# 02.net
KiCad netlist of a schematic drawn in Altium Designer
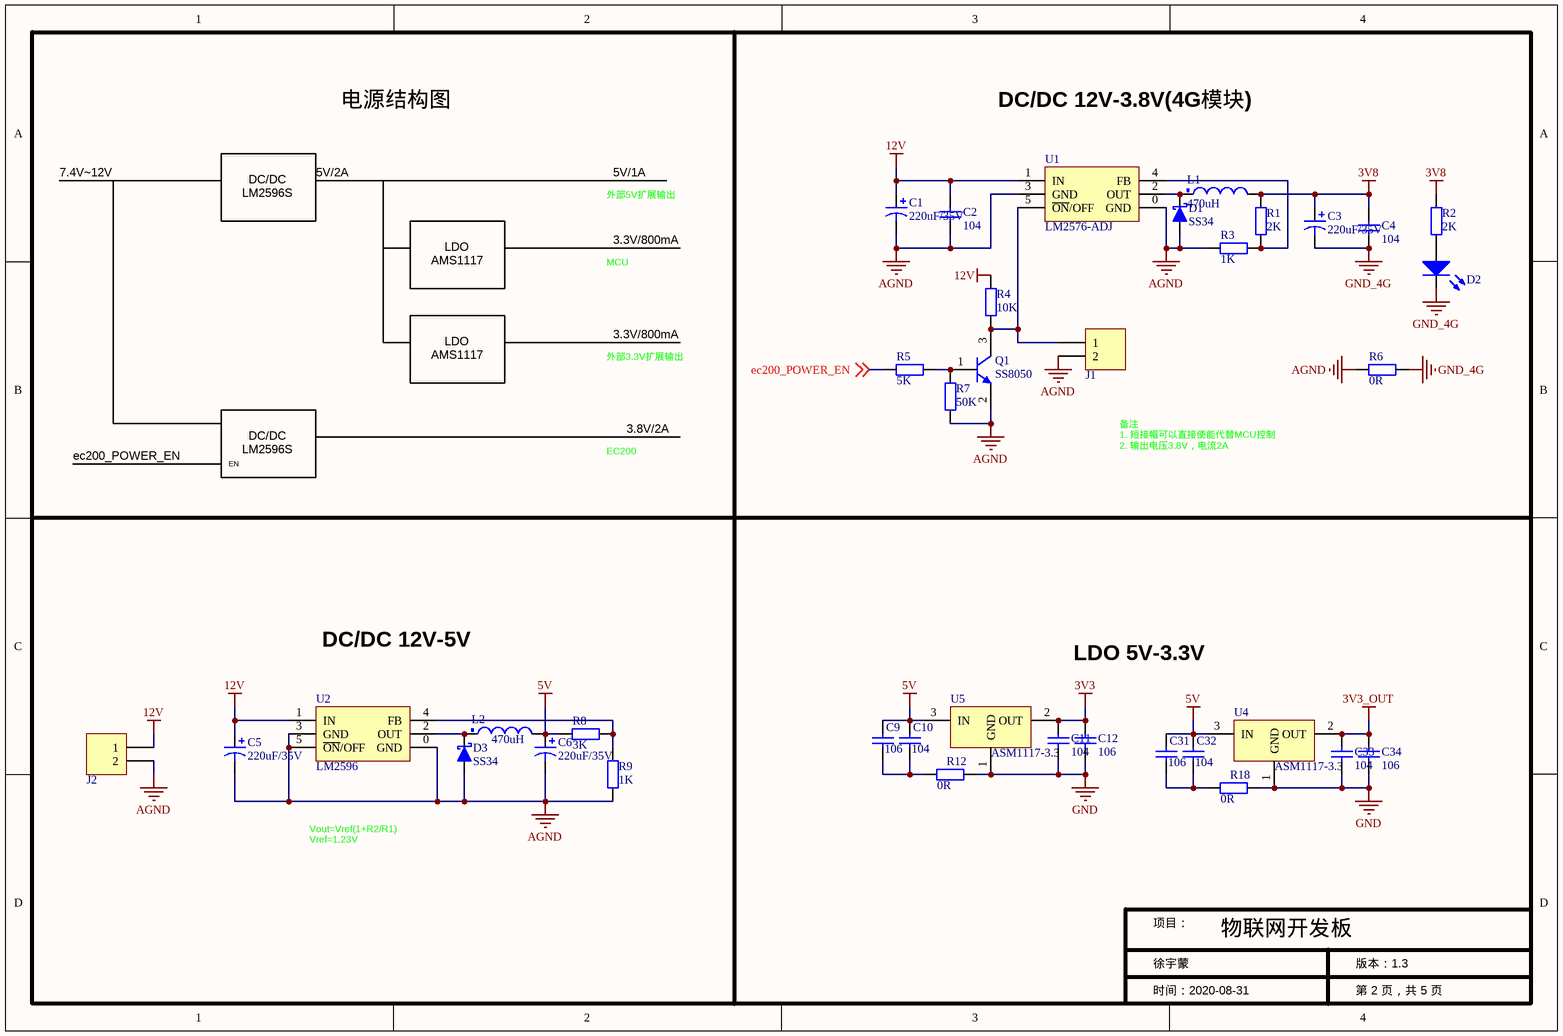
[diagram p0: 02_电源部分.SchDoc]

(export (version "E")
  (design (tool "Eeschema 10.0.6"))
  (components
    (comp (ref "C1")
      (value "220uF/35V")
      (footprint "Cap8x10.5mm")
      (description "贴片电解电容 8*10.5mm")
      (fields (field (name "Comment") "Cap Pol") (field (name "PUBLISHER") "Altium Limited"))
      (libsource (lib "元件库") (part "Cap Pol"))
    )
    (comp (ref "C2")
      (value "104")
      (footprint "CAP-0603")
      (description "无极性电容")
      (fields (field (name "Comment") "Cap") (field (name "PUBLISHER") "Altium Limited"))
      (libsource (lib "Arrowy_Racing") (part "Cap"))
    )
    (comp (ref "C3")
      (value "220uF/35V")
      (footprint "Cap8x10.5mm")
      (description "贴片电解电容 8*10.5mm")
      (fields (field (name "Comment") "Cap Pol") (field (name "PUBLISHER") "Altium Limited"))
      (libsource (lib "元件库") (part "Cap Pol"))
    )
    (comp (ref "C4")
      (value "104")
      (footprint "CAP-0603")
      (description "无极性电容")
      (fields (field (name "Comment") "Cap") (field (name "PUBLISHER") "Altium Limited"))
      (libsource (lib "Arrowy_Racing") (part "Cap"))
    )
    (comp (ref "C5")
      (value "220uF/35V")
      (footprint "Cap8x10.5mm")
      (description "贴片电解电容 8*10.5mm")
      (fields (field (name "Comment") "Cap Pol") (field (name "PUBLISHER") "Altium Limited"))
      (libsource (lib "元件库") (part "Cap Pol"))
    )
    (comp (ref "C6")
      (value "220uF/35V")
      (footprint "Cap8x10.5mm")
      (description "贴片电解电容 8*10.5mm")
      (fields (field (name "Comment") "Cap Pol") (field (name "PUBLISHER") "Altium Limited"))
      (libsource (lib "元件库") (part "Cap Pol"))
    )
    (comp (ref "C9")
      (value "106")
      (footprint "CAP-0603")
      (description "无极性电容")
      (fields (field (name "Comment") "Cap") (field (name "PUBLISHER") "Altium Limited"))
      (libsource (lib "Arrowy_Racing") (part "Cap"))
    )
    (comp (ref "C10")
      (value "104")
      (footprint "CAP-0603")
      (description "无极性电容")
      (fields (field (name "Comment") "Cap") (field (name "PUBLISHER") "Altium Limited"))
      (libsource (lib "Arrowy_Racing") (part "Cap"))
    )
    (comp (ref "C11")
      (value "104")
      (footprint "CAP-0603")
      (description "无极性电容")
      (fields (field (name "Comment") "Cap") (field (name "PUBLISHER") "Altium Limited"))
      (libsource (lib "Arrowy_Racing") (part "Cap"))
    )
    (comp (ref "C12")
      (value "106")
      (footprint "CAP-0603")
      (description "无极性电容")
      (fields (field (name "Comment") "Cap") (field (name "PUBLISHER") "Altium Limited"))
      (libsource (lib "Arrowy_Racing") (part "Cap"))
    )
    (comp (ref "C31")
      (value "106")
      (footprint "CAP-0603")
      (description "无极性电容")
      (fields (field (name "Comment") "Cap") (field (name "PUBLISHER") "Altium Limited"))
      (libsource (lib "Arrowy_Racing") (part "Cap"))
    )
    (comp (ref "C32")
      (value "104")
      (footprint "CAP-0603")
      (description "无极性电容")
      (fields (field (name "Comment") "Cap") (field (name "PUBLISHER") "Altium Limited"))
      (libsource (lib "Arrowy_Racing") (part "Cap"))
    )
    (comp (ref "C33")
      (value "104")
      (footprint "CAP-0603")
      (description "无极性电容")
      (fields (field (name "Comment") "Cap") (field (name "PUBLISHER") "Altium Limited"))
      (libsource (lib "Arrowy_Racing") (part "Cap"))
    )
    (comp (ref "C34")
      (value "106")
      (footprint "CAP-0603")
      (description "无极性电容")
      (fields (field (name "Comment") "Cap") (field (name "PUBLISHER") "Altium Limited"))
      (libsource (lib "Arrowy_Racing") (part "Cap"))
    )
    (comp (ref "D1")
      (value "SS34")
      (footprint "SMA(DO-214AC)")
      (description "Schottky Diode")
      (fields (field (name "PUBLISHER") "Altium Limited"))
      (libsource (lib "元件库") (part "D Schottky"))
    )
    (comp (ref "D2")
      (value "LED")
      (footprint "LED_0805")
      (description "发光二极管")
      (fields (field (name "PUBLISHER") "Altium Limited"))
      (libsource (lib "Arrowy_Racing") (part "LED"))
    )
    (comp (ref "D3")
      (value "SS34")
      (footprint "SMA(DO-214AC)")
      (description "Schottky Diode")
      (fields (field (name "PUBLISHER") "Altium Limited"))
      (libsource (lib "元件库") (part "D Schottky"))
    )
    (comp (ref "J1")
      (value "Header 2")
      (footprint "Header_2X1_2.54")
      (description "接插件")
      (fields (field (name "PUBLISHER") "Altium Limited"))
      (libsource (lib "") (part "Header 2_1"))
    )
    (comp (ref "J2")
      (value "Header 2")
      (footprint "Header_HT_2P_5.08_Right")
      (description "接插件")
      (fields (field (name "PUBLISHER") "Altium Limited"))
      (libsource (lib "Arrowy_Racing") (part "Header 2"))
    )
    (comp (ref "L1")
      (value "470uH")
      (footprint "CD43")
      (description "贴片功率电感")
      (fields (field (name "Comment") "Inductor") (field (name "PUBLISHER") "Altium Limited"))
      (libsource (lib "元件库") (part "Inductor"))
    )
    (comp (ref "L2")
      (value "470uH")
      (footprint "CD43")
      (description "贴片功率电感")
      (fields (field (name "Comment") "Inductor") (field (name "PUBLISHER") "Altium Limited"))
      (libsource (lib "元件库") (part "Inductor"))
    )
    (comp (ref "Q1")
      (value "SS8050")
      (footprint "SOT-23")
      (description "NPN贴片三极管")
      (fields (field (name "PUBLISHER") "Altium Limited"))
      (libsource (lib "Arrowy_Racing") (part "SS8050"))
    )
    (comp (ref "R1")
      (value "2K")
      (footprint "0603")
      (description "贴片电阻")
      (fields (field (name "Comment") "Res") (field (name "PUBLISHER") "Altium Limited"))
      (libsource (lib "Arrowy_Racing") (part "Res"))
    )
    (comp (ref "R2")
      (value "2K")
      (footprint "0603")
      (description "贴片电阻")
      (fields (field (name "Comment") "Res") (field (name "PUBLISHER") "Altium Limited"))
      (libsource (lib "") (part "Res_2"))
    )
    (comp (ref "R3")
      (value "1K")
      (footprint "0603")
      (description "贴片电阻")
      (fields (field (name "Comment") "Res") (field (name "PUBLISHER") "Altium Limited"))
      (libsource (lib "") (part "Res_1"))
    )
    (comp (ref "R4")
      (value "10K")
      (footprint "0603")
      (description "贴片电阻")
      (fields (field (name "Comment") "Res") (field (name "PUBLISHER") "Altium Limited"))
      (libsource (lib "Arrowy_Racing") (part "Res"))
    )
    (comp (ref "R5")
      (value "5K")
      (footprint "0603")
      (description "贴片电阻")
      (fields (field (name "Comment") "Res") (field (name "PUBLISHER") "Altium Limited"))
      (libsource (lib "") (part "Res_1"))
    )
    (comp (ref "R6")
      (value "0R")
      (footprint "0805")
      (description "贴片电阻")
      (fields (field (name "Comment") "Res") (field (name "PUBLISHER") "Altium Limited"))
      (libsource (lib "") (part "Res_1"))
    )
    (comp (ref "R7")
      (value "50K")
      (footprint "0603")
      (description "贴片电阻")
      (fields (field (name "Comment") "Res") (field (name "PUBLISHER") "Altium Limited"))
      (libsource (lib "Arrowy_Racing") (part "Res"))
    )
    (comp (ref "R8")
      (value "3K")
      (footprint "0603")
      (description "贴片电阻")
      (fields (field (name "Comment") "Res") (field (name "PUBLISHER") "Altium Limited"))
      (libsource (lib "") (part "Res_1"))
    )
    (comp (ref "R9")
      (value "1K")
      (footprint "0603")
      (description "贴片电阻")
      (fields (field (name "Comment") "Res") (field (name "PUBLISHER") "Altium Limited"))
      (libsource (lib "") (part "Res_2"))
    )
    (comp (ref "R12")
      (value "0R")
      (footprint "0805")
      (description "贴片电阻")
      (fields (field (name "Comment") "Res") (field (name "PUBLISHER") "Altium Limited"))
      (libsource (lib "") (part "Res_1"))
    )
    (comp (ref "R18")
      (value "0R")
      (footprint "0805")
      (description "贴片电阻")
      (fields (field (name "Comment") "Res") (field (name "PUBLISHER") "Altium Limited"))
      (libsource (lib "") (part "Res_1"))
    )
    (comp (ref "U1")
      (value "LM2576-ADJ")
      (footprint "TO-263-5 无背面散热")
      (libsource (lib "Arrowy_Racing") (part "LM2576"))
    )
    (comp (ref "U2")
      (value "LM2596")
      (footprint "TO-263-5 无背面散热")
      (description "DC/DC")
      (libsource (lib "Arrowy_Racing") (part "LM2596"))
    )
    (comp (ref "U4")
      (value "ASM1117-3.3")
      (footprint "SOT-223")
      (description "3.3V稳压芯片")
      (libsource (lib "Arrowy_Racing") (part "ASM1117"))
    )
    (comp (ref "U5")
      (value "ASM1117-3.3")
      (footprint "SOT-223")
      (description "3.3V稳压芯片")
      (libsource (lib "Arrowy_Racing") (part "ASM1117"))
    )
  )
  (nets
    (net (code "1") (name "3V3") (class "Default")
      (node (ref "C11") (pin "2") (pinfunction "2_2") (pintype "passive"))
      (node (ref "C12") (pin "2") (pinfunction "2_2") (pintype "passive"))
      (node (ref "U5") (pin "2") (pinfunction "OUT_2") (pintype "passive"))
    )
    (net (code "2") (name "3V3_OUT") (class "Default")
      (node (ref "C33") (pin "2") (pinfunction "2_2") (pintype "passive"))
      (node (ref "C34") (pin "2") (pinfunction "2_2") (pintype "passive"))
      (node (ref "U4") (pin "2") (pinfunction "OUT_2") (pintype "passive"))
    )
    (net (code "3") (name "3V8") (class "Default")
      (node (ref "C3") (pin "1") (pinfunction "1_1") (pintype "passive"))
      (node (ref "C4") (pin "2") (pinfunction "2_2") (pintype "passive"))
      (node (ref "L1") (pin "2") (pinfunction "2_2") (pintype "passive"))
      (node (ref "R1") (pin "1") (pinfunction "1_1") (pintype "passive"))
      (node (ref "R2") (pin "2") (pinfunction "2_2") (pintype "passive"))
    )
    (net (code "4") (name "5V") (class "Default")
      (node (ref "C10") (pin "2") (pinfunction "2_2") (pintype "passive"))
      (node (ref "C31") (pin "2") (pinfunction "2_2") (pintype "passive"))
      (node (ref "C32") (pin "2") (pinfunction "2_2") (pintype "passive"))
      (node (ref "C6") (pin "1") (pinfunction "1_1") (pintype "passive"))
      (node (ref "C9") (pin "2") (pinfunction "2_2") (pintype "passive"))
      (node (ref "L2") (pin "2") (pinfunction "2_2") (pintype "passive"))
      (node (ref "R8") (pin "1") (pinfunction "1_1") (pintype "passive"))
      (node (ref "U4") (pin "3") (pinfunction "IN_3") (pintype "passive"))
      (node (ref "U5") (pin "3") (pinfunction "IN_3") (pintype "passive"))
    )
    (net (code "5") (name "12V") (class "Default")
      (node (ref "C1") (pin "1") (pinfunction "1_1") (pintype "passive"))
      (node (ref "C2") (pin "2") (pinfunction "2_2") (pintype "passive"))
      (node (ref "C5") (pin "1") (pinfunction "1_1") (pintype "passive"))
      (node (ref "J2") (pin "1") (pinfunction "1_1") (pintype "passive"))
      (node (ref "R4") (pin "1") (pinfunction "1_1") (pintype "passive"))
      (node (ref "U1") (pin "1") (pinfunction "IN_1") (pintype "passive"))
      (node (ref "U2") (pin "1") (pinfunction "IN_1") (pintype "passive"))
    )
    (net (code "6") (name "AGND") (class "Default")
      (node (ref "C1") (pin "2") (pinfunction "2_2") (pintype "passive"))
      (node (ref "C2") (pin "1") (pinfunction "1_1") (pintype "passive"))
      (node (ref "C5") (pin "2") (pinfunction "2_2") (pintype "passive"))
      (node (ref "C6") (pin "2") (pinfunction "2_2") (pintype "passive"))
      (node (ref "D1") (pin "1") (pinfunction "A_1") (pintype "passive"))
      (node (ref "D3") (pin "1") (pinfunction "A_1") (pintype "passive"))
      (node (ref "J1") (pin "2") (pinfunction "2_2") (pintype "passive"))
      (node (ref "J2") (pin "2") (pinfunction "2_2") (pintype "passive"))
      (node (ref "Q1") (pin "2") (pinfunction "E_2") (pintype "passive"))
      (node (ref "R3") (pin "1") (pinfunction "1_1") (pintype "passive"))
      (node (ref "R6") (pin "1") (pinfunction "1_1") (pintype "passive"))
      (node (ref "R7") (pin "2") (pinfunction "2_2") (pintype "passive"))
      (node (ref "R9") (pin "1") (pinfunction "1_1") (pintype "passive"))
      (node (ref "U1") (pin "0") (pinfunction "GND_0") (pintype "passive"))
      (node (ref "U1") (pin "3") (pinfunction "GND_3") (pintype "passive"))
      (node (ref "U2") (pin "0") (pinfunction "GND_0") (pintype "passive"))
      (node (ref "U2") (pin "3") (pinfunction "GND_3") (pintype "passive"))
      (node (ref "U2") (pin "5") (pinfunction "~{ON}/OFF_5") (pintype "passive"))
    )
    (net (code "7") (name "GND") (class "Default")
      (node (ref "C11") (pin "1") (pinfunction "1_1") (pintype "passive"))
      (node (ref "C12") (pin "1") (pinfunction "1_1") (pintype "passive"))
      (node (ref "C33") (pin "1") (pinfunction "1_1") (pintype "passive"))
      (node (ref "C34") (pin "1") (pinfunction "1_1") (pintype "passive"))
      (node (ref "R12") (pin "2") (pinfunction "2_2") (pintype "passive"))
      (node (ref "R18") (pin "2") (pinfunction "2_2") (pintype "passive"))
      (node (ref "U4") (pin "1") (pinfunction "GND_1") (pintype "passive"))
      (node (ref "U5") (pin "1") (pinfunction "GND_1") (pintype "passive"))
    )
    (net (code "8") (name "GND_4G") (class "Default")
      (node (ref "C3") (pin "2") (pinfunction "2_2") (pintype "passive"))
      (node (ref "C4") (pin "1") (pinfunction "1_1") (pintype "passive"))
      (node (ref "D2") (pin "2") (pinfunction "K_2") (pintype "passive"))
      (node (ref "R6") (pin "2") (pinfunction "2_2") (pintype "passive"))
    )
    (net (code "9") (name "Net-(C10-Pad1)") (class "Default")
      (node (ref "C10") (pin "1") (pinfunction "1_1") (pintype "passive"))
      (node (ref "C9") (pin "1") (pinfunction "1_1") (pintype "passive"))
      (node (ref "R12") (pin "1") (pinfunction "1_1") (pintype "passive"))
    )
    (net (code "10") (name "Net-(C31-Pad1)") (class "Default")
      (node (ref "C31") (pin "1") (pinfunction "1_1") (pintype "passive"))
      (node (ref "C32") (pin "1") (pinfunction "1_1") (pintype "passive"))
      (node (ref "R18") (pin "1") (pinfunction "1_1") (pintype "passive"))
    )
    (net (code "11") (name "Net-(D1-K)") (class "Default")
      (node (ref "D1") (pin "2") (pinfunction "K_2") (pintype "passive"))
      (node (ref "L1") (pin "1") (pinfunction "1_1") (pintype "passive"))
      (node (ref "U1") (pin "2") (pinfunction "OUT_2") (pintype "passive"))
    )
    (net (code "12") (name "Net-(D2-A)") (class "Default")
      (node (ref "D2") (pin "1") (pinfunction "A_1") (pintype "passive"))
      (node (ref "R2") (pin "1") (pinfunction "1_1") (pintype "passive"))
    )
    (net (code "13") (name "Net-(D3-K)") (class "Default")
      (node (ref "D3") (pin "2") (pinfunction "K_2") (pintype "passive"))
      (node (ref "L2") (pin "1") (pinfunction "1_1") (pintype "passive"))
      (node (ref "U2") (pin "2") (pinfunction "OUT_2") (pintype "passive"))
    )
    (net (code "14") (name "Net-(Q1-B)") (class "Default")
      (node (ref "Q1") (pin "1") (pinfunction "B_1") (pintype "passive"))
      (node (ref "R5") (pin "2") (pinfunction "2_2") (pintype "passive"))
      (node (ref "R7") (pin "1") (pinfunction "1_1") (pintype "passive"))
    )
    (net (code "15") (name "Net-(Q1-C)") (class "Default")
      (node (ref "J1") (pin "1") (pinfunction "1_1") (pintype "passive"))
      (node (ref "Q1") (pin "3") (pinfunction "C_3") (pintype "passive"))
      (node (ref "R4") (pin "2") (pinfunction "2_2") (pintype "passive"))
      (node (ref "U1") (pin "5") (pinfunction "~{ON}/OFF_5") (pintype "passive"))
    )
    (net (code "16") (name "Net-(U1-FB)") (class "Default")
      (node (ref "R1") (pin "2") (pinfunction "2_2") (pintype "passive"))
      (node (ref "R3") (pin "2") (pinfunction "2_2") (pintype "passive"))
      (node (ref "U1") (pin "4") (pinfunction "FB_4") (pintype "passive"))
    )
    (net (code "17") (name "Net-(U2-FB)") (class "Default")
      (node (ref "R8") (pin "2") (pinfunction "2_2") (pintype "passive"))
      (node (ref "R9") (pin "2") (pinfunction "2_2") (pintype "passive"))
      (node (ref "U2") (pin "4") (pinfunction "FB_4") (pintype "passive"))
    )
    (net (code "18") (name "ec200_POWER_EN") (class "Default")
      (node (ref "R5") (pin "1") (pinfunction "1_1") (pintype "passive"))
    )
  )
)
